# Simple_Oscillator.net
KiCad netlist of a schematic drawn in Altium Designer
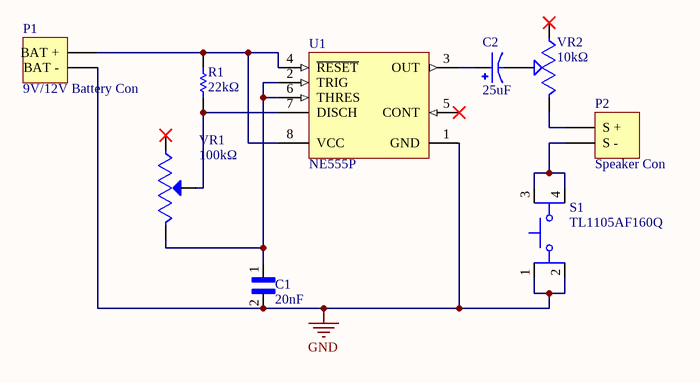
[diagram p0: Simple Oscillator.SchDoc]

(export (version "E")
  (design (tool "Eeschema 10.0.6"))
  (components
    (comp (ref "C1")
      (value "20nF")
      (footprint "CC0603KRX7R9BB203")
      (description "X7R 20nF 50V 0603 Multilayer Ceramic Capacitors MLCC - SMD/SMT ROHS")
      (fields (field (name "MANUFACTURER") "YAGEO") (field (name "LCSC PART#") "C282065"))
      (libsource (lib "CC0603KRX7R9BB203") (part "CC0603KRX7R9BB203"))
    )
    (comp (ref "C2")
      (value "25uF")
      (footprint "EEUED2C250U")
      (description "Aluminum Electrolytic Capacitors, ED-A Series, 25uF +/- 20%, 160V, Radial lead type(10x16mm)")
      (fields (field (name "MANUFACTURER") "Panasonic") (field (name "MFR.PART #") "EEUED2C250U"))
      (libsource (lib "EEUED2C250U") (part "EEUED2C250U"))
    )
    (comp (ref "P1")
      (value "9V/12V Battery Con")
      (footprint "HDR1X2")
      (description "Header, 2-Pin")
      (fields (field (name "PUBLISHER") "Altium Limited"))
      (libsource (lib "") (part "Header 2_1"))
    )
    (comp (ref "P2")
      (value "Speaker Con")
      (footprint "HDR1X2")
      (description "Header, 2-Pin")
      (fields (field (name "PUBLISHER") "Altium Limited"))
      (libsource (lib "Miscellaneous Connectors") (part "Header 2"))
    )
    (comp (ref "R1")
      (value "22kΩ")
      (footprint "RESC1005X40X25NL05T10")
      (fields
        (field (name "MANUFACTURER") " YAGEO")
        (field (name "MFR.PART #") "RC0402FR-0722KL")
        (field (name "LCSC PART#") "C82868")
      )
      (libsource (lib "Altium Content Vault") (part "RES"))
    )
    (comp (ref "S1")
      (value "TL1105AF160Q")
      (footprint "TL1105AF160Q")
      (description "6mm 1.4mm Round Button 50mA Straight 6mm SPST 12V Plugin,6x6mm Tactile Switches ROHS")
      (fields (field (name "MANUFACTURER") "E-Switch") (field (name "LCSC PART#") "C273465"))
      (libsource (lib "TL1105AF160Q") (part "TL1105AF160Q"))
    )
    (comp (ref "U1")
      (value "NE555P")
      (footprint "P0008A")
      (description "4.5V~16V 0℃~+70℃ 10mA DIP-8 Timers / Clock Oscillators ROHS")
      (fields (field (name "MANUFACTURER") "Texas Instruments") (field (name "LCSC PART#") "C46749"))
      (libsource (lib "Altium Content Vault") (part "TI-NE555-P8"))
    )
    (comp (ref "VR1")
      (value "100kΩ")
      (footprint "3296W-1-104")
      (description "±10% 100kΩ Plugin Variable Resistors/Potentiometers ROHS")
      (fields (field (name "LCSC PART#") "C330435") (field (name "MFR.PART #") "3296W-1-104"))
      (libsource (lib "3296W-1-104") (part "3296W-1-104"))
    )
    (comp (ref "VR2")
      (value "10kΩ")
      (footprint "3296X-1-103")
      (description "±10% 10kΩ Plugin Variable Resistors/Potentiometers ROHS")
      (fields
        (field (name "MFR. PART #") "3296X-1-103")
        (field (name "MANUFACTURER") "BOCHEN(Chengdu Guosheng Tech)")
      )
      (libsource (lib "3296X-1-103") (part "3296X-1-103"))
    )
  )
  (nets
    (net (code "1") (name "GND") (class "Default")
      (node (ref "C1") (pin "2") (pinfunction "2_2") (pintype "passive"))
      (node (ref "P1") (pin "1") (pinfunction "BAT_-_1") (pintype "passive"))
      (node (ref "S1") (pin "1") (pinfunction "1_1") (pintype "passive"))
      (node (ref "S1") (pin "2") (pinfunction "2_2") (pintype "passive"))
      (node (ref "U1") (pin "1") (pinfunction "GND_1") (pintype "power_in"))
    )
    (net (code "2") (name "Net-(P1-BAT_+)") (class "Default")
      (node (ref "P1") (pin "2") (pinfunction "BAT_+_2") (pintype "passive"))
      (node (ref "R1") (pin "2") (pinfunction "2_2") (pintype "passive"))
      (node (ref "U1") (pin "4") (pinfunction "~{RESET}_4") (pintype "input"))
      (node (ref "U1") (pin "8") (pinfunction "VCC_8") (pintype "power_in"))
    )
    (net (code "3") (name "Net-(P2-S_+)") (class "Default")
      (node (ref "P2") (pin "1") (pinfunction "S_+_1") (pintype "passive"))
      (node (ref "VR2") (pin "3") (pinfunction "C_3") (pintype "passive"))
    )
    (net (code "4") (name "Net-(P2-S_-)") (class "Default")
      (node (ref "P2") (pin "2") (pinfunction "S_-_2") (pintype "passive"))
      (node (ref "S1") (pin "3") (pinfunction "3_3") (pintype "passive"))
      (node (ref "S1") (pin "4") (pinfunction "4_4") (pintype "passive"))
    )
    (net (code "5") (name "Net-(U1-DISCH)") (class "Default")
      (node (ref "R1") (pin "1") (pinfunction "1_1") (pintype "passive"))
      (node (ref "U1") (pin "7") (pinfunction "DISCH_7") (pintype "open_collector"))
      (node (ref "VR1") (pin "2") (pinfunction "WIPER_2") (pintype "passive"))
    )
    (net (code "6") (name "Net-(U1-OUT)") (class "Default")
      (node (ref "C2") (pin "P") (pinfunction "P_P") (pintype "passive"))
      (node (ref "U1") (pin "3") (pinfunction "OUT_3") (pintype "output"))
    )
    (net (code "7") (name "Net-(U1-THRES)") (class "Default")
      (node (ref "C1") (pin "1") (pinfunction "1_1") (pintype "passive"))
      (node (ref "U1") (pin "2") (pinfunction "TRIG_2") (pintype "input"))
      (node (ref "U1") (pin "6") (pinfunction "THRES_6") (pintype "input"))
      (node (ref "VR1") (pin "3") (pinfunction "CW_3") (pintype "passive"))
    )
    (net (code "8") (name "Net-(VR2-B)") (class "Default")
      (node (ref "C2") (pin "N") (pinfunction "N_N") (pintype "passive"))
      (node (ref "VR2") (pin "2") (pinfunction "B_2") (pintype "passive"))
    )
    (net (code "9") (name "unconnected-(U1-CONT-Pad5)") (class "Default")
      (node (ref "U1") (pin "5") (pinfunction "CONT_5") (pintype "input+no_connect"))
    )
    (net (code "10") (name "unconnected-(VR1-CCW-Pad1)") (class "Default")
      (node (ref "VR1") (pin "1") (pinfunction "CCW_1") (pintype "passive+no_connect"))
    )
    (net (code "11") (name "unconnected-(VR2-A-Pad1)") (class "Default")
      (node (ref "VR2") (pin "1") (pinfunction "A_1") (pintype "passive+no_connect"))
    )
  )
)
